# ch340g-uart.net
KiCad netlist of a schematic drawn in EAGLE
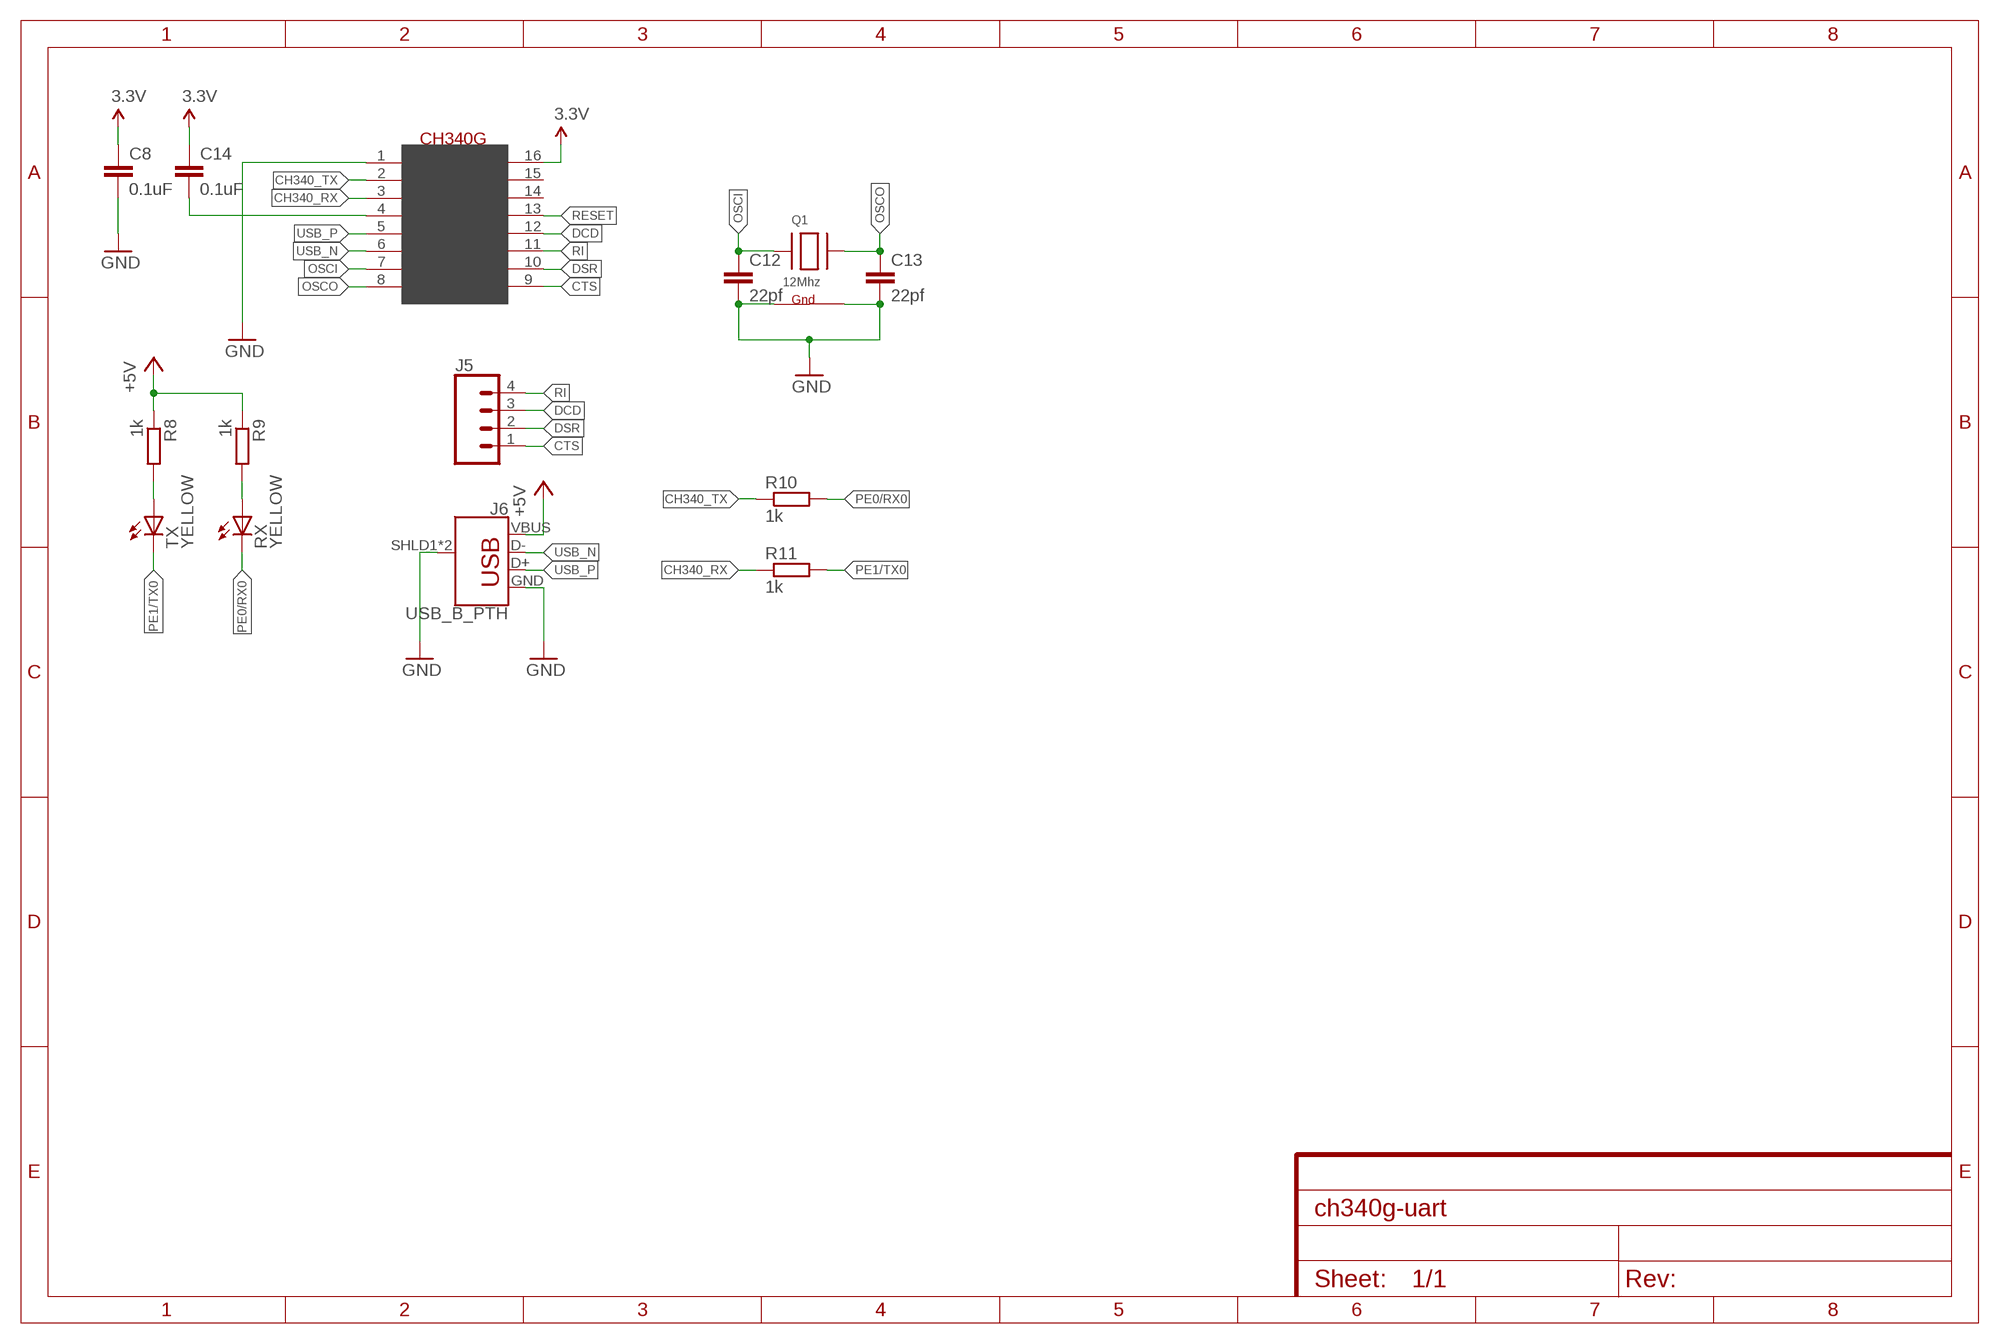
[diagram p0: schematic, sheet 1]

(export (version "E")
  (design (tool "Eeschema 10.0.6"))
  (components
    (comp (ref "C8")
      (value "0.1uF")
      (footprint "eagle-import:C1206")
      (libsource (lib "eagle-import") (part "rcl_334_C-EUC1206"))
    )
    (comp (ref "C12")
      (value "22pf")
      (footprint "eagle-import:C1206")
      (libsource (lib "eagle-import") (part "C-EUC1206"))
    )
    (comp (ref "C13")
      (value "22pf")
      (footprint "eagle-import:C1206")
      (libsource (lib "eagle-import") (part "C-EUC1206"))
    )
    (comp (ref "C14")
      (value "0.1uF")
      (footprint "eagle-import:C1206")
      (libsource (lib "eagle-import") (part "rcl_334_C-EUC1206"))
    )
    (comp (ref "IC3")
      (value "CH340G")
      (footprint "eagle-import:SOIC16")
      (libsource (lib "eagle-import") (part "CH340G"))
    )
    (comp (ref "J5")
      (value "CONN_04")
      (footprint "eagle-import:1X04")
      (libsource (lib "eagle-import") (part "CONN_04"))
    )
    (comp (ref "J6")
      (value "USB_B_PTH")
      (footprint "eagle-import:USB-B-PTH")
      (libsource (lib "eagle-import") (part "USB_B_PTH"))
    )
    (comp (ref "Q1")
      (value "12Mhz")
      (footprint "eagle-import:NX3225")
      (libsource (lib "eagle-import") (part "XTAL-4-3225"))
    )
    (comp (ref "R8")
      (value "1k")
      (footprint "eagle-import:R1206")
      (libsource (lib "eagle-import") (part "R-EU_R1206"))
    )
    (comp (ref "R9")
      (value "1k")
      (footprint "eagle-import:R1206")
      (libsource (lib "eagle-import") (part "R-EU_R1206"))
    )
    (comp (ref "R10")
      (value "1k")
      (footprint "eagle-import:R1206")
      (libsource (lib "eagle-import") (part "R-EU_R1206"))
    )
    (comp (ref "R11")
      (value "1k")
      (footprint "eagle-import:R1206")
      (libsource (lib "eagle-import") (part "R-EU_R1206"))
    )
    (comp (ref "RX")
      (value "YELLOW")
      (footprint "eagle-import:CHIP-LED0805")
      (libsource (lib "eagle-import") (part "LEDCHIP-LED0805"))
    )
    (comp (ref "TX")
      (value "YELLOW")
      (footprint "eagle-import:CHIP-LED0805")
      (libsource (lib "eagle-import") (part "LEDCHIP-LED0805"))
    )
  )
  (nets
    (net (code "1") (name "+5V") (class "Default")
      (node (ref "J6") (pin "VBUS") (pinfunction "VBUS_VBUS") (pintype "power_in"))
      (node (ref "R8") (pin "1") (pinfunction "1_1") (pintype "passive"))
      (node (ref "R9") (pin "1") (pinfunction "1_1") (pintype "passive"))
    )
    (net (code "2") (name "3.3V") (class "Default")
      (node (ref "C14") (pin "1") (pinfunction "1_1") (pintype "passive"))
      (node (ref "C8") (pin "1") (pinfunction "1_1") (pintype "passive"))
      (node (ref "IC3") (pin "16") (pinfunction "VCC_16") (pintype "bidirectional"))
    )
    (net (code "3") (name "CH340_RX") (class "Default")
      (node (ref "IC3") (pin "3") (pinfunction "RX_3") (pintype "bidirectional"))
      (node (ref "R11") (pin "1") (pinfunction "1_1") (pintype "passive"))
    )
    (net (code "4") (name "CH340_TX") (class "Default")
      (node (ref "IC3") (pin "2") (pinfunction "TX_2") (pintype "bidirectional"))
      (node (ref "R10") (pin "1") (pinfunction "1_1") (pintype "passive"))
    )
    (net (code "5") (name "CTS") (class "Default")
      (node (ref "IC3") (pin "9") (pinfunction "CTS_9") (pintype "bidirectional"))
      (node (ref "J5") (pin "1") (pinfunction "1_1") (pintype "passive"))
    )
    (net (code "6") (name "DCD") (class "Default")
      (node (ref "IC3") (pin "12") (pinfunction "DCD_12") (pintype "bidirectional"))
      (node (ref "J5") (pin "3") (pinfunction "3_3") (pintype "passive"))
    )
    (net (code "7") (name "DSR") (class "Default")
      (node (ref "IC3") (pin "10") (pinfunction "DSR_10") (pintype "bidirectional"))
      (node (ref "J5") (pin "2") (pinfunction "2_2") (pintype "passive"))
    )
    (net (code "8") (name "GND") (class "Default")
      (node (ref "C12") (pin "2") (pinfunction "2_2") (pintype "passive"))
      (node (ref "C13") (pin "2") (pinfunction "2_2") (pintype "passive"))
      (node (ref "C8") (pin "2") (pinfunction "2_2") (pintype "passive"))
      (node (ref "IC3") (pin "1") (pinfunction "GND_1") (pintype "bidirectional"))
      (node (ref "J6") (pin "GND") (pinfunction "GND_GND") (pintype "power_in"))
      (node (ref "J6") (pin "SHLD1") (pinfunction "SHIELD_SHLD1") (pintype "bidirectional"))
      (node (ref "J6") (pin "SHLD2") (pinfunction "SHIELD_SHLD2") (pintype "bidirectional"))
      (node (ref "Q1") (pin "2") (pinfunction "G2_2") (pintype "power_in"))
      (node (ref "Q1") (pin "4") (pinfunction "G1_4") (pintype "power_in"))
    )
    (net (code "9") (name "Net-(IC3-V3)") (class "Default")
      (node (ref "C14") (pin "2") (pinfunction "2_2") (pintype "passive"))
      (node (ref "IC3") (pin "4") (pinfunction "V3_4") (pintype "bidirectional"))
    )
    (net (code "10") (name "Net-(R8-Pad2)") (class "Default")
      (node (ref "R8") (pin "2") (pinfunction "2_2") (pintype "passive"))
      (node (ref "TX") (pin "A") (pinfunction "A_A") (pintype "passive"))
    )
    (net (code "11") (name "Net-(R9-Pad2)") (class "Default")
      (node (ref "R9") (pin "2") (pinfunction "2_2") (pintype "passive"))
      (node (ref "RX") (pin "A") (pinfunction "A_A") (pintype "passive"))
    )
    (net (code "12") (name "OSCI") (class "Default")
      (node (ref "C12") (pin "1") (pinfunction "1_1") (pintype "passive"))
      (node (ref "IC3") (pin "7") (pinfunction "XI_7") (pintype "bidirectional"))
      (node (ref "Q1") (pin "1") (pinfunction "X1_1") (pintype "bidirectional"))
    )
    (net (code "13") (name "OSCO") (class "Default")
      (node (ref "C13") (pin "1") (pinfunction "1_1") (pintype "passive"))
      (node (ref "IC3") (pin "8") (pinfunction "XO_8") (pintype "bidirectional"))
      (node (ref "Q1") (pin "3") (pinfunction "X2_3") (pintype "bidirectional"))
    )
    (net (code "14") (name "PE0{slash}RX0") (class "Default")
      (node (ref "R10") (pin "2") (pinfunction "2_2") (pintype "passive"))
      (node (ref "RX") (pin "C") (pinfunction "C_C") (pintype "passive"))
    )
    (net (code "15") (name "PE1{slash}TX0") (class "Default")
      (node (ref "R11") (pin "2") (pinfunction "2_2") (pintype "passive"))
      (node (ref "TX") (pin "C") (pinfunction "C_C") (pintype "passive"))
    )
    (net (code "16") (name "RESET") (class "Default")
      (node (ref "IC3") (pin "13") (pinfunction "DTR_13") (pintype "bidirectional"))
    )
    (net (code "17") (name "RI") (class "Default")
      (node (ref "IC3") (pin "11") (pinfunction "RI_11") (pintype "bidirectional"))
      (node (ref "J5") (pin "4") (pinfunction "4_4") (pintype "passive"))
    )
    (net (code "18") (name "USB_N") (class "Default")
      (node (ref "IC3") (pin "6") (pinfunction "D-_6") (pintype "bidirectional"))
      (node (ref "J6") (pin "D-") (pinfunction "D-_D-") (pintype "bidirectional"))
    )
    (net (code "19") (name "USB_P") (class "Default")
      (node (ref "IC3") (pin "5") (pinfunction "D+_5") (pintype "bidirectional"))
      (node (ref "J6") (pin "D+") (pinfunction "D+_D+") (pintype "bidirectional"))
    )
    (net (code "20") (name "unconnected-(IC3-RS232-Pad15)") (class "Default")
      (node (ref "IC3") (pin "15") (pinfunction "RS232_15") (pintype "bidirectional"))
    )
    (net (code "21") (name "unconnected-(IC3-RTS-Pad14)") (class "Default")
      (node (ref "IC3") (pin "14") (pinfunction "RTS_14") (pintype "bidirectional"))
    )
  )
)
